# Environmental_Sensors.net
KiCad netlist of a schematic drawn in Altium Designer
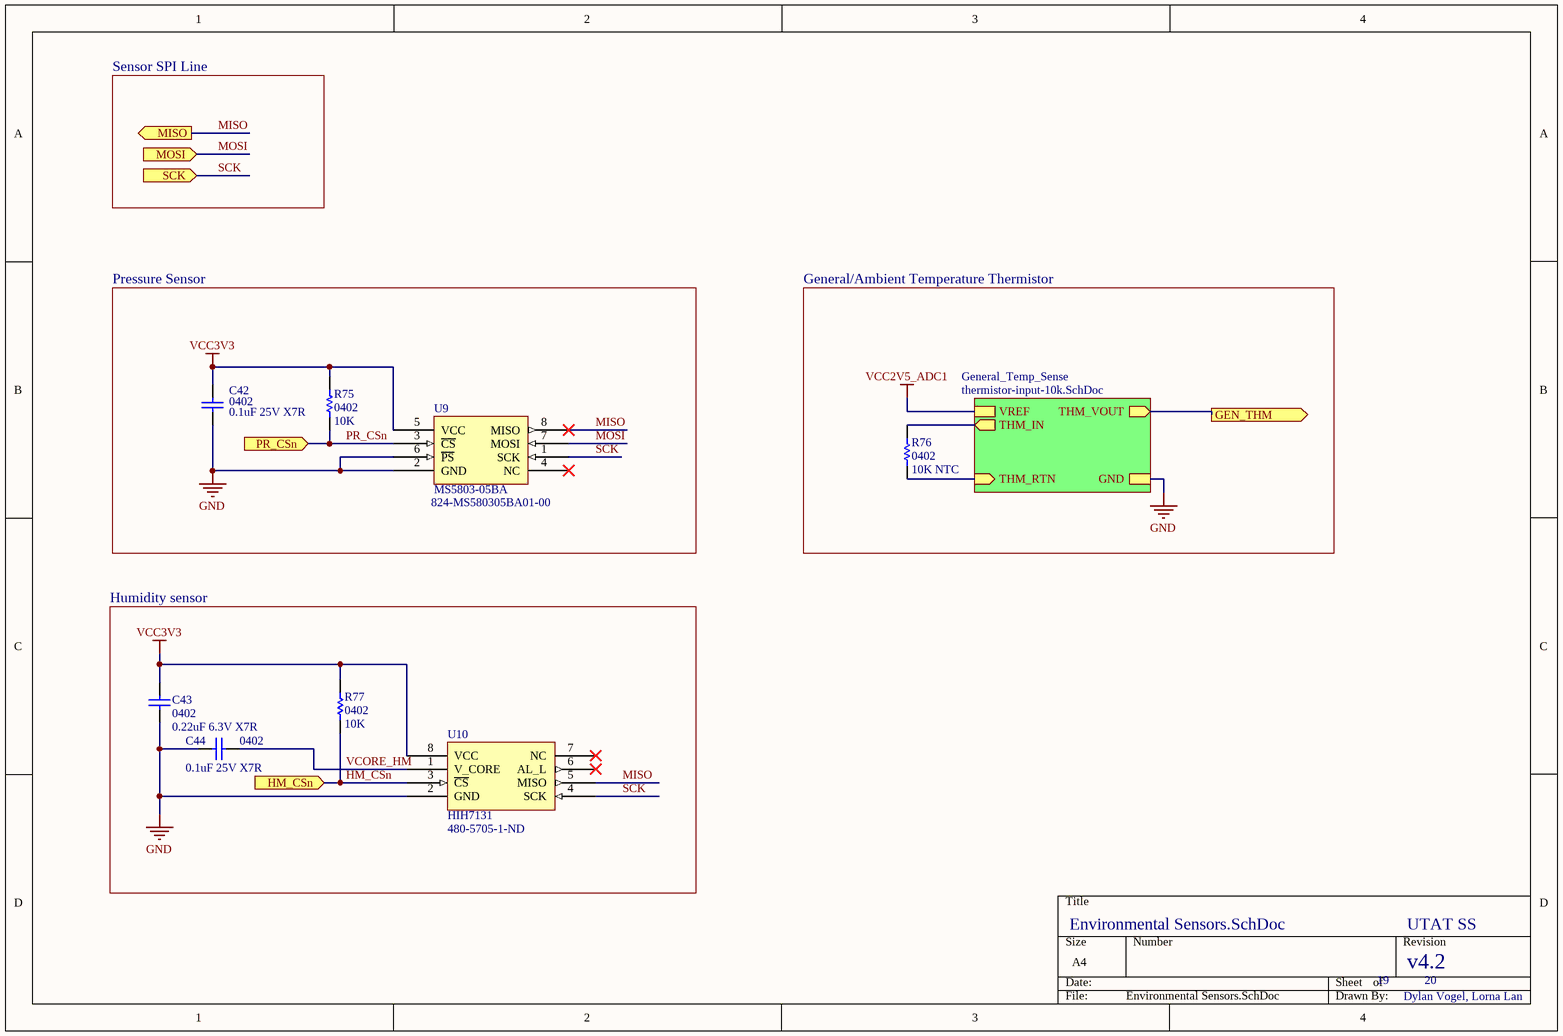
[diagram p0: Environmental Sensors.SchDoc]

(export (version "E")
  (design (tool "Eeschema 10.0.6"))
  (components
    (comp (ref "C42")
      (value "0402")
      (footprint "CAP0402R")
      (description "0402 capacitor")
      (fields (field (name "ALTIUM_VALUE") "0.1uF 25V X7R"))
      (libsource (lib "heron-general") (part "CAP0402"))
    )
    (comp (ref "C43")
      (value "0402")
      (footprint "CAP0402R")
      (description "0402 capacitor")
      (fields (field (name "ALTIUM_VALUE") "0.22uF 6.3V X7R"))
      (libsource (lib "CAP0402") (part "CAP0402"))
    )
    (comp (ref "C44")
      (value "0402")
      (footprint "CAP0402R")
      (description "0402 capacitor")
      (fields (field (name "ALTIUM_VALUE") "0.1uF 25V X7R"))
      (libsource (lib "heron-general") (part "CAP0402"))
    )
    (comp (ref "R75")
      (value "0402")
      (footprint "RES0402R")
      (description "0402 resistor")
      (fields
        (field (name "ALTIUM_VALUE") "10K")
        (field (name "MANUFACTURER") "Panasonic")
        (field (name "MANUFACTURER PART NUMBER") "ERJ-2RKF1002X")
      )
      (libsource (lib "heron-general") (part "RES0402"))
    )
    (comp (ref "R76")
      (value "0402")
      (footprint "RES0402R")
      (description "0402 resistor")
      (fields (field (name "ALTIUM_VALUE") "10K NTC"))
      (libsource (lib "heron-general") (part "RES0402"))
    )
    (comp (ref "R77")
      (value "0402")
      (footprint "RES0402R")
      (description "0402 resistor")
      (fields
        (field (name "ALTIUM_VALUE") "10K")
        (field (name "MANUFACTURER") "Panasonic")
        (field (name "MANUFACTURER PART NUMBER") "ERJ-2RKF1002X")
      )
      (libsource (lib "heron-general") (part "RES0402"))
    )
    (comp (ref "U9")
      (value "MS5803-05BA")
      (footprint "MS5803_125P640x620-8N")
      (fields (field (name "SUPPLIER PART NUMBER 1") "824-MS580305BA01-00"))
      (libsource (lib "PAY") (part "MS5803-05BA"))
    )
    (comp (ref "U10")
      (value "HIH7131")
      (footprint "SOIC127P500X600-8N")
      (fields (field (name "SUPPLIER PART NUMBER 1") "480-5705-1-ND"))
      (libsource (lib "PAY") (part "HIH7131"))
    )
  )
  (nets
    (net (code "2") (name "/HM_CSn") (class "Default")
      (node (ref "R77") (pin "1") (pinfunction "1_1") (pintype "passive"))
      (node (ref "U10") (pin "3") (pinfunction "~{CS}_3") (pintype "input"))
    )
    (net (code "3") (name "/MISO") (class "Default")
      (node (ref "U10") (pin "5") (pinfunction "MISO_5") (pintype "output"))
      (node (ref "U9") (pin "8") (pinfunction "MISO_8") (pintype "output"))
    )
    (net (code "4") (name "/MOSI") (class "Default")
      (node (ref "U9") (pin "7") (pinfunction "MOSI_7") (pintype "input"))
    )
    (net (code "5") (name "/PR_CSn") (class "Default")
      (node (ref "R75") (pin "1") (pinfunction "1_1") (pintype "passive"))
      (node (ref "U9") (pin "3") (pinfunction "~{CS}_3") (pintype "input"))
    )
    (net (code "6") (name "/SCK") (class "Default")
      (node (ref "U10") (pin "4") (pinfunction "SCK_4") (pintype "input"))
      (node (ref "U9") (pin "1") (pinfunction "SCK_1") (pintype "input"))
    )
    (net (code "7") (name "/THM_IN") (class "Default")
      (node (ref "R76") (pin "2") (pinfunction "2_2") (pintype "passive"))
    )
    (net (code "8") (name "/THM_RTN") (class "Default")
      (node (ref "R76") (pin "1") (pinfunction "1_1") (pintype "passive"))
    )
    (net (code "9") (name "/VCORE_HM") (class "Default")
      (node (ref "C44") (pin "2") (pinfunction "2_2") (pintype "passive"))
      (node (ref "U10") (pin "1") (pinfunction "V_CORE_1") (pintype "power_in"))
    )
    (net (code "10") (name "GND") (class "Default")
      (node (ref "C42") (pin "1") (pinfunction "1_1") (pintype "passive"))
      (node (ref "C43") (pin "1") (pinfunction "1_1") (pintype "passive"))
      (node (ref "C44") (pin "1") (pinfunction "1_1") (pintype "passive"))
      (node (ref "U10") (pin "2") (pinfunction "GND_2") (pintype "power_in"))
      (node (ref "U9") (pin "2") (pinfunction "GND_2") (pintype "power_in"))
      (node (ref "U9") (pin "6") (pinfunction "~{PS}_6") (pintype "input"))
    )
    (net (code "12") (name "VCC3V3") (class "Default")
      (node (ref "C42") (pin "2") (pinfunction "2_2") (pintype "passive"))
      (node (ref "C43") (pin "2") (pinfunction "2_2") (pintype "passive"))
      (node (ref "R75") (pin "2") (pinfunction "2_2") (pintype "passive"))
      (node (ref "R77") (pin "2") (pinfunction "2_2") (pintype "passive"))
      (node (ref "U10") (pin "8") (pinfunction "VCC_8") (pintype "power_in"))
      (node (ref "U9") (pin "5") (pinfunction "VCC_5") (pintype "power_in"))
    )
    (net (code "13") (name "unconnected-(U9-NC-Pad4)") (class "Default")
      (node (ref "U9") (pin "4") (pinfunction "NC_4") (pintype "passive+no_connect"))
    )
    (net (code "14") (name "unconnected-(U10-AL_L-Pad6)") (class "Default")
      (node (ref "U10") (pin "6") (pinfunction "AL_L_6") (pintype "output+no_connect"))
    )
    (net (code "15") (name "unconnected-(U10-NC-Pad7)") (class "Default")
      (node (ref "U10") (pin "7") (pinfunction "NC_7") (pintype "passive+no_connect"))
    )
  )
)
